# SAMD21_Xplained_Pro_triple_input_power_s.net
KiCad netlist of a schematic drawn in Altium Designer
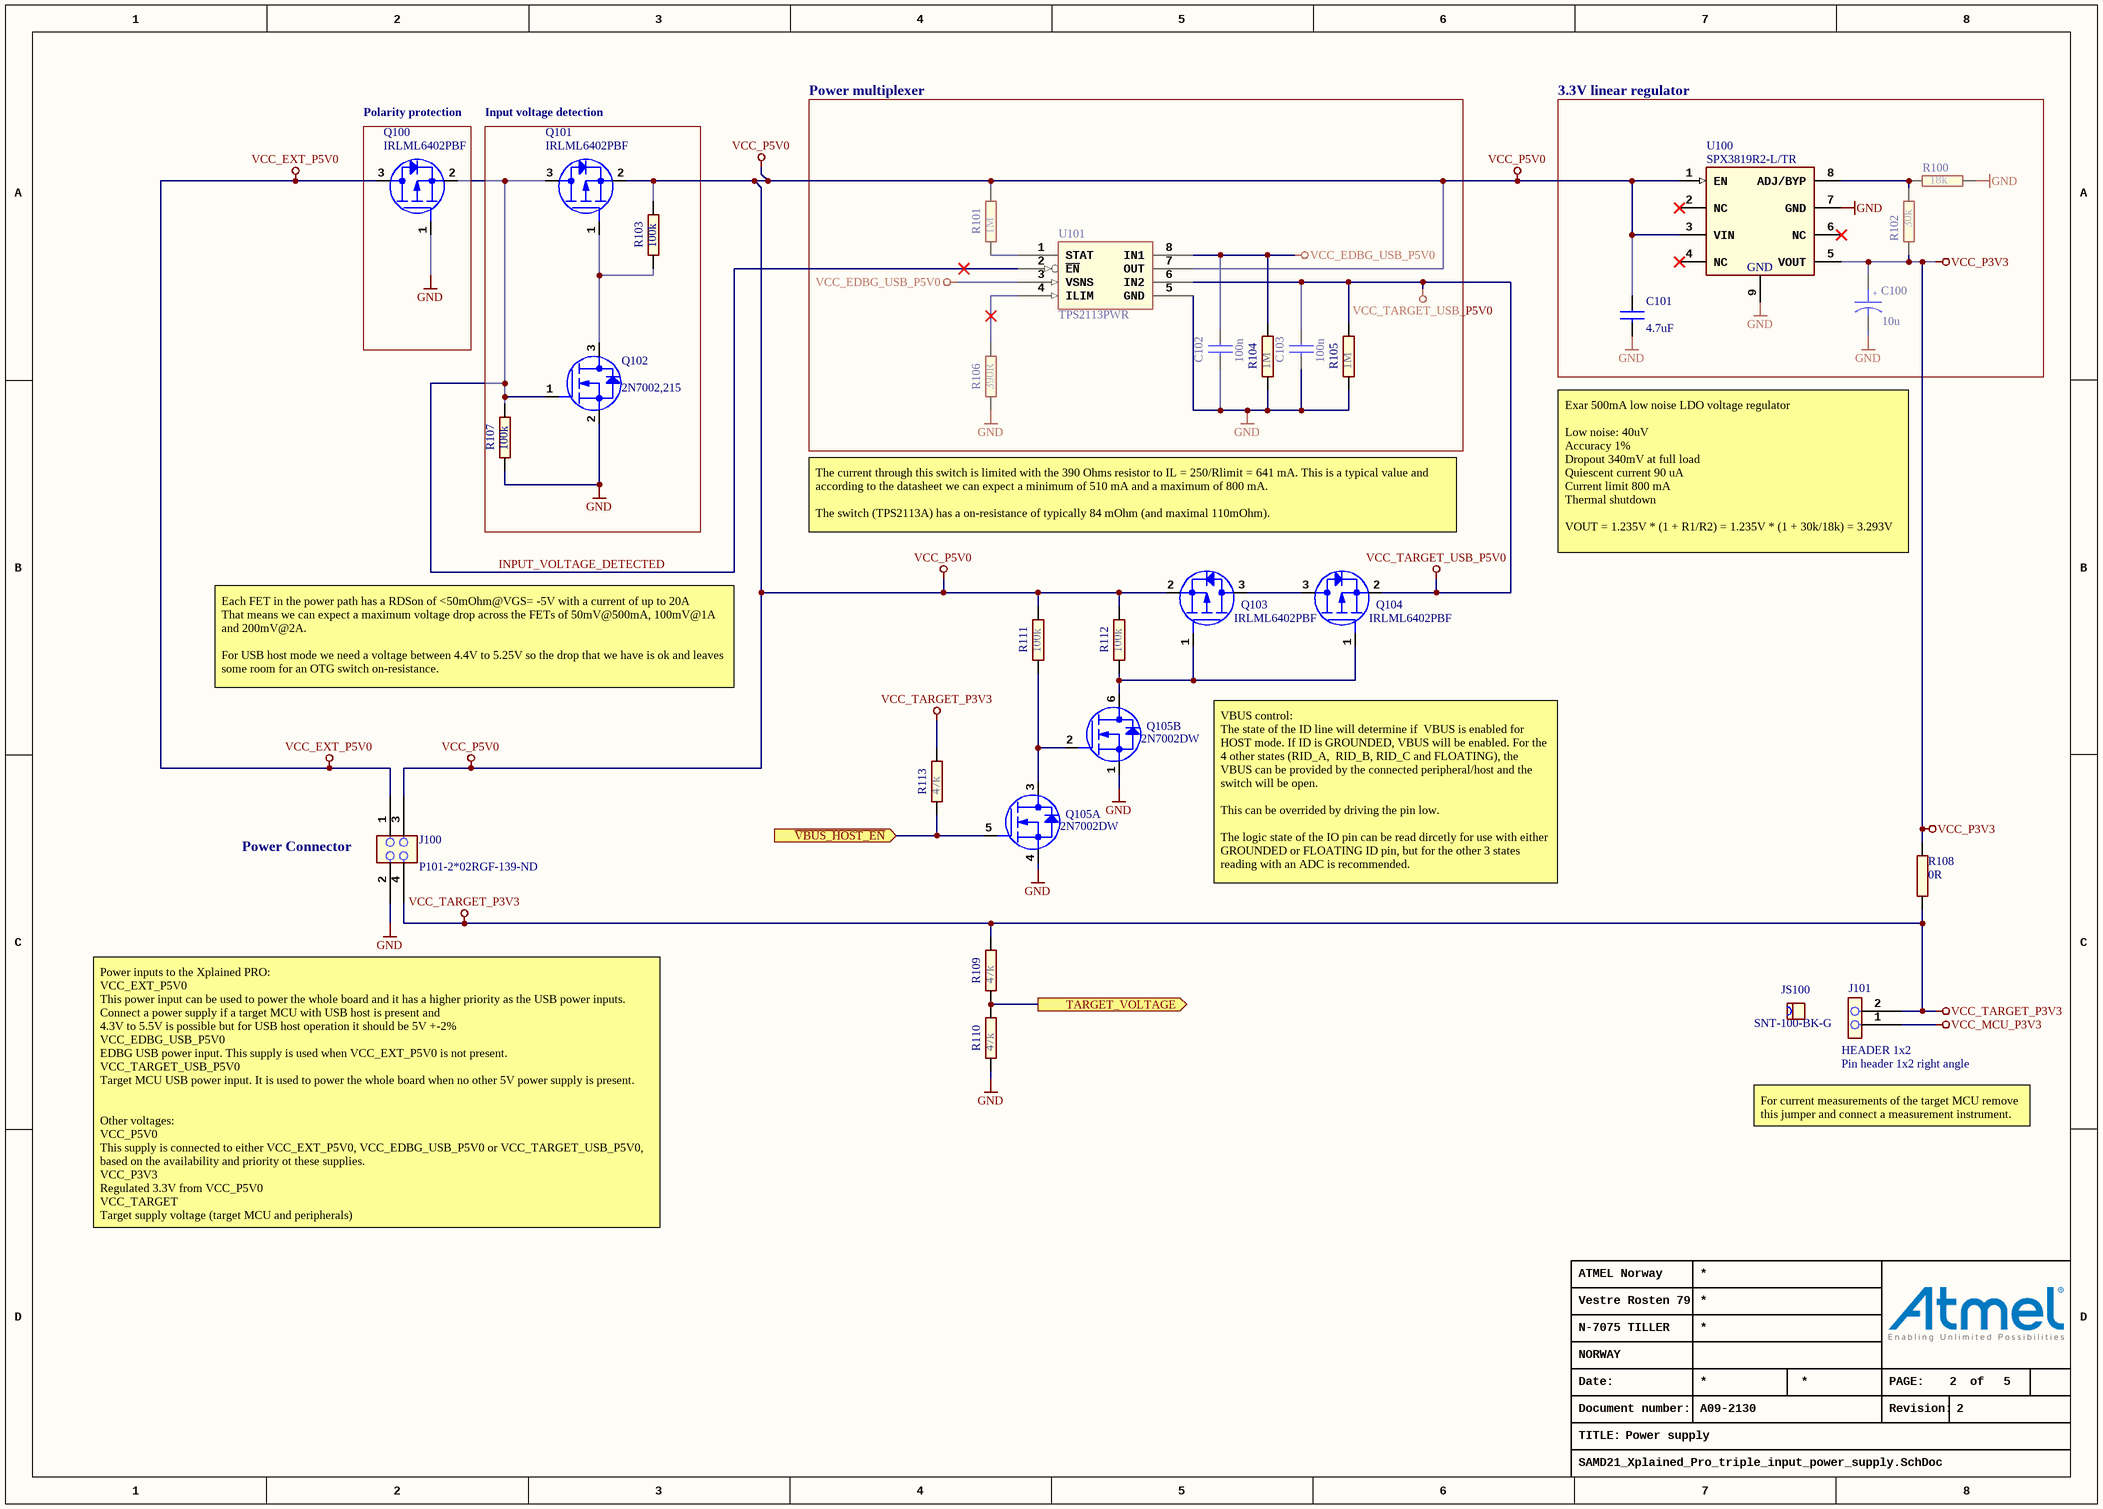
[diagram p0: SAMD21_Xplained_Pro_triple_input_power_supply.SchDoc]

(export (version "E")
  (design (tool "Eeschema 10.0.6"))
  (components
    (comp (ref "C100")
      (value "10u")
      (footprint "AP1-00036")
      (description "SMD tantalum capacitor, ESR = 1.7, 3216-18 (EIA) 1206,")
      (fields (field (name "TOLERANCE") "+-10%") (field (name "MANUFACTURER") "vishay"))
      (libsource (lib "AltiumDbLib") (part "CAP-POL"))
    )
    (comp (ref "C101")
      (value "4.7uF")
      (footprint "AP1-00039")
      (description "Ceramic capacitor, SMD 0603, X5R, 10V, 10% (de31036)")
      (fields (field (name "TOLERANCE") "10%") (field (name "MANUFACTURER") "tdk"))
      (libsource (lib "AltiumDbLib") (part "CAP-NONPOL"))
    )
    (comp (ref "C102")
      (value "100n")
      (footprint "AP1-00001")
      (description "Ceramic capacitor, SMD 0402, X7R, 16V, +/-10%")
      (fields (field (name "TOLERANCE") "16V, +/-10%") (field (name "MANUFACTURER") "Kemet"))
      (libsource (lib "AltiumDbLib") (part "CAP-NONPOL"))
    )
    (comp (ref "C103")
      (value "100n")
      (footprint "AP1-00001")
      (description "Ceramic capacitor, SMD 0402, X7R, 16V, +/-10%")
      (fields (field (name "TOLERANCE") "16V, +/-10%") (field (name "MANUFACTURER") "Kemet"))
      (libsource (lib "AltiumDbLib") (part "CAP-NONPOL"))
    )
    (comp (ref "J100")
      (value "P101-2*02RGF-139-ND")
      (footprint "AP8-00628")
      (description "Pin header, 2x2, Right Angle, 2.54mm, THT, Pin In Paste")
      (fields (field (name "Comment") "HEADER 2x2"))
      (libsource (lib "AltiumDbLib") (part "HEADER 2x2"))
    )
    (comp (ref "J101")
      (value "HEADER 1x2")
      (footprint "AP8-00367")
      (description "1x2 pin header, right angle, 2.54 mm pitch, through-hole")
      (fields
        (field (name "ALTIUM_VALUE") "Pin header 1x2 right angle")
        (field (name "MANUFACTURER") "Pro-data International Corp")
        (field (name "MPN") "2213R-2G")
      )
      (libsource (lib "AltiumDbLib") (part "HEADER 1x2"))
    )
    (comp (ref "JS100")
      (value "SNT-100-BK-G")
      (footprint "AP8-00525")
      (description "Jumper cap for 2.54mm pinheader")
      (fields (field (name "MANUFACTURER") "SAMTEC"))
      (libsource (lib "AltiumDbLib") (part "JUMPER_CAP"))
    )
    (comp (ref "Q100")
      (value "IRLML6402PBF")
      (footprint "AP5-00002")
      (description "P-ch. MOSFET. -30V, -3.7A continuous,RDS(ON)=0.05Ohm@VGS=-4,5V, RDS(ON)=0.08Ohm@VGS=-2.5V")
      (fields (field (name "MANUFACTURER") "International Rectifier") (field (name "Comment") "MOSFET_P_GSD"))
      (libsource (lib "AltiumDbLib") (part "MOSFET_P_GSD"))
    )
    (comp (ref "Q101")
      (value "IRLML6402PBF")
      (footprint "AP5-00002")
      (description "P-ch. MOSFET. -30V, -3.7A continuous,RDS(ON)=0.05Ohm@VGS=-4,5V, RDS(ON)=0.08Ohm@VGS=-2.5V")
      (fields (field (name "MANUFACTURER") "International Rectifier") (field (name "Comment") "MOSFET_P_GSD"))
      (libsource (lib "AltiumDbLib") (part "MOSFET_P_GSD"))
    )
    (comp (ref "Q102")
      (value "2N7002,215")
      (footprint "AP5-00002")
      (description "N-Channel MOSFET. 60V, 0.300A continuous, 1.2A Peak. RDS(ON) = 3.8Ohm@VGS=4.5V, VGS(th)<2.5V")
      (fields (field (name "MANUFACTURER") "NXP") (field (name "Comment") "MOSFET_N_GSD"))
      (libsource (lib "AltiumDbLib") (part "MOSFET_N_GSD"))
    )
    (comp (ref "Q103")
      (value "IRLML6402PBF")
      (footprint "AP5-00002")
      (description "P-ch. MOSFET. -30V, -3.7A continuous,RDS(ON)=0.05Ohm@VGS=-4,5V, RDS(ON)=0.08Ohm@VGS=-2.5V")
      (fields (field (name "MANUFACTURER") "International Rectifier") (field (name "Comment") "MOSFET_P_GSD"))
      (libsource (lib "AltiumDbLib") (part "MOSFET_P_GSD"))
    )
    (comp (ref "Q104")
      (value "IRLML6402PBF")
      (footprint "AP5-00002")
      (description "P-ch. MOSFET. -30V, -3.7A continuous,RDS(ON)=0.05Ohm@VGS=-4,5V, RDS(ON)=0.08Ohm@VGS=-2.5V")
      (fields (field (name "MANUFACTURER") "International Rectifier") (field (name "Comment") "MOSFET_P_GSD"))
      (libsource (lib "AltiumDbLib") (part "MOSFET_P_GSD"))
    )
    (comp (ref "Q105")
      (value "2N7002DW")
      (footprint "AP5-00001")
      (description "Dual N-Channel MOSFET, 60V, 115mA cont,RDS(ON) < 7.5 Ohm @50mA@5V, SOT-363")
      (fields
        (field (name "MANUFACTURER") "Fairchild")
        (field (name "Comment") "Same as 2N7002 but with two MOSFETs in one package")
      )
      (libsource (lib "AltiumDbLib") (part "MOSFET_DUAL_N_S2G2D1S1G1D2"))
    )
    (comp (ref "R100")
      (value "18k")
      (footprint "AP2-00000")
      (description "Thick film resistor, SMD 0402, 1/16W, 1%")
      (fields (field (name "TOLERANCE") "1 %") (field (name "Comment") "R2"))
      (libsource (lib "") (part "R2_3"))
    )
    (comp (ref "R101")
      (value "1M")
      (footprint "AP2-00000")
      (description "Thick film resistor, SMD 0402, 1/16W, 1%")
      (fields (field (name "TOLERANCE") "1 %") (field (name "Comment") "R2"))
      (libsource (lib "") (part "R2_1"))
    )
    (comp (ref "R102")
      (value "30k")
      (footprint "AP2-00000")
      (description "Thick film resistor, SMD 0402, 1/16W, 1%")
      (fields (field (name "TOLERANCE") "1 %") (field (name "Comment") "R2"))
      (libsource (lib "") (part "R2_1"))
    )
    (comp (ref "R103")
      (value "100k")
      (footprint "AP2-00000")
      (description "Thick film resistor, SMD 0402, 1/16W, 1%")
      (fields (field (name "TOLERANCE") "1 %") (field (name "Comment") "R2"))
      (libsource (lib "") (part "R2_1"))
    )
    (comp (ref "R104")
      (value "1M")
      (footprint "AP2-00000")
      (description "Thick film resistor, SMD 0402, 1/16W, 1%")
      (fields (field (name "TOLERANCE") "1 %") (field (name "Comment") "R2"))
      (libsource (lib "") (part "R2_1"))
    )
    (comp (ref "R105")
      (value "1M")
      (footprint "AP2-00000")
      (description "Thick film resistor, SMD 0402, 1/16W, 1%")
      (fields (field (name "TOLERANCE") "1 %") (field (name "Comment") "R2"))
      (libsource (lib "") (part "R2_1"))
    )
    (comp (ref "R106")
      (value "390R")
      (footprint "AP2-00000")
      (description "Thick film resistor, SMD 0402, 1/16W, 1%")
      (fields (field (name "TOLERANCE") "1 %") (field (name "Comment") "R2"))
      (libsource (lib "") (part "R2_1"))
    )
    (comp (ref "R107")
      (value "100k")
      (footprint "AP2-00000")
      (description "Thick film resistor, SMD 0402, 1/16W, 1%")
      (fields (field (name "TOLERANCE") "1 %") (field (name "Comment") "R2"))
      (libsource (lib "") (part "R2_1"))
    )
    (comp (ref "R108")
      (value "0R")
      (footprint "AP2-00000")
      (description "Thick film resistor, SMD 0402, 1/16W, 1%")
      (fields (field (name "TOLERANCE") "1 %") (field (name "Comment") "R2"))
      (libsource (lib "AltiumDbLib") (part "R2"))
    )
    (comp (ref "R109")
      (value "47k")
      (footprint "AP2-00000")
      (description "Thick film resistor, SMD 0402, 1/16W, 1%")
      (fields (field (name "TOLERANCE") "1 %") (field (name "Comment") "R2"))
      (libsource (lib "") (part "R2_2"))
    )
    (comp (ref "R110")
      (value "47k")
      (footprint "AP2-00000")
      (description "Thick film resistor, SMD 0402, 1/16W, 1%")
      (fields (field (name "TOLERANCE") "1 %") (field (name "Comment") "R2"))
      (libsource (lib "") (part "R2_2"))
    )
    (comp (ref "R111")
      (value "100k")
      (footprint "AP2-00000")
      (description "Thick film resistor, SMD 0402, 1/16W, 1%")
      (fields (field (name "TOLERANCE") "1 %") (field (name "Comment") "R2"))
      (libsource (lib "") (part "R2_1"))
    )
    (comp (ref "R112")
      (value "100k")
      (footprint "AP2-00000")
      (description "Thick film resistor, SMD 0402, 1/16W, 1%")
      (fields (field (name "TOLERANCE") "1 %") (field (name "Comment") "R2"))
      (libsource (lib "AltiumDbLib") (part "R2"))
    )
    (comp (ref "R113")
      (value "47k")
      (footprint "AP2-00000")
      (description "Thick film resistor, SMD 0402, 1/16W, 1%")
      (fields (field (name "TOLERANCE") "1 %") (field (name "Comment") "R2"))
      (libsource (lib "") (part "R2_2"))
    )
    (comp (ref "U100")
      (value "SPX3819R2-L/TR")
      (footprint "AP6-00338")
      (description "500mA LDO, ADJ, low noise, 8-DFN package")
      (fields (field (name "TOLERANCE") "±1%") (field (name "MANUFACTURER") "Exar"))
      (libsource (lib "AltiumDbLib") (part "SPX3819R2-L"))
    )
    (comp (ref "U101")
      (value "TPS2113PWR")
      (footprint "AP6-00054")
      (description "Autoswitching 2:1 Power Mux")
      (fields (field (name "MANUFACTURER") "Texas Instruments") (field (name "Comment") "TPS2112"))
      (libsource (lib "AltiumDbLib") (part "TPS2112"))
    )
  )
  (nets
    (net (code "1") (name "/INPUT_VOLTAGE_DETECTED") (class "Default")
      (node (ref "Q100") (pin "2") (pinfunction "S_2") (pintype "passive"))
      (node (ref "Q101") (pin "3") (pinfunction "D_3") (pintype "passive"))
      (node (ref "Q102") (pin "1") (pinfunction "G_1") (pintype "passive"))
      (node (ref "R107") (pin "2") (pinfunction "2_2") (pintype "passive"))
      (node (ref "U101") (pin "2") (pinfunction "~{EN}_2") (pintype "input"))
    )
    (net (code "2") (name "/TARGET_VOLTAGE") (class "Default")
      (node (ref "R109") (pin "1") (pinfunction "1_1") (pintype "passive"))
      (node (ref "R110") (pin "2") (pinfunction "2_2") (pintype "passive"))
    )
    (net (code "3") (name "/~{VBUS_HOST_EN}") (class "Default")
      (node (ref "Q105") (pin "5") (pinfunction "G1_5") (pintype "passive"))
      (node (ref "R113") (pin "1") (pinfunction "1_1") (pintype "passive"))
    )
    (net (code "4") (name "GND") (class "Default")
      (node (ref "C100") (pin "2") (pinfunction "2_2") (pintype "passive"))
      (node (ref "C101") (pin "2") (pinfunction "2_2") (pintype "passive"))
      (node (ref "C102") (pin "2") (pinfunction "2_2") (pintype "passive"))
      (node (ref "C103") (pin "2") (pinfunction "2_2") (pintype "passive"))
      (node (ref "J100") (pin "2") (pinfunction "2_2") (pintype "passive"))
      (node (ref "Q100") (pin "1") (pinfunction "G_1") (pintype "passive"))
      (node (ref "Q102") (pin "2") (pinfunction "S_2") (pintype "passive"))
      (node (ref "Q105") (pin "1") (pinfunction "S2_1") (pintype "passive"))
      (node (ref "Q105") (pin "4") (pinfunction "S1_4") (pintype "passive"))
      (node (ref "R100") (pin "2") (pinfunction "2_2") (pintype "passive"))
      (node (ref "R104") (pin "1") (pinfunction "1_1") (pintype "passive"))
      (node (ref "R105") (pin "1") (pinfunction "1_1") (pintype "passive"))
      (node (ref "R106") (pin "1") (pinfunction "1_1") (pintype "passive"))
      (node (ref "R107") (pin "1") (pinfunction "1_1") (pintype "passive"))
      (node (ref "R110") (pin "1") (pinfunction "1_1") (pintype "passive"))
      (node (ref "U100") (pin "7") (pinfunction "GND_7") (pintype "power_in"))
      (node (ref "U100") (pin "9") (pinfunction "GND_9") (pintype "power_in"))
      (node (ref "U101") (pin "5") (pinfunction "GND_5") (pintype "power_in"))
    )
    (net (code "5") (name "Net-(Q101-G)") (class "Default")
      (node (ref "Q101") (pin "1") (pinfunction "G_1") (pintype "passive"))
      (node (ref "Q102") (pin "3") (pinfunction "D_3") (pintype "passive"))
      (node (ref "R103") (pin "1") (pinfunction "1_1") (pintype "passive"))
    )
    (net (code "6") (name "Net-(Q103-D)") (class "Default")
      (node (ref "Q103") (pin "3") (pinfunction "D_3") (pintype "passive"))
      (node (ref "Q104") (pin "3") (pinfunction "D_3") (pintype "passive"))
    )
    (net (code "7") (name "Net-(Q103-G)") (class "Default")
      (node (ref "Q103") (pin "1") (pinfunction "G_1") (pintype "passive"))
      (node (ref "Q104") (pin "1") (pinfunction "G_1") (pintype "passive"))
      (node (ref "Q105") (pin "6") (pinfunction "D2_6") (pintype "passive"))
      (node (ref "R112") (pin "2") (pinfunction "2_2") (pintype "passive"))
    )
    (net (code "8") (name "Net-(Q105A-D1)") (class "Default")
      (node (ref "Q105") (pin "2") (pinfunction "G2_2") (pintype "passive"))
      (node (ref "Q105") (pin "3") (pinfunction "D1_3") (pintype "passive"))
      (node (ref "R111") (pin "1") (pinfunction "1_1") (pintype "passive"))
    )
    (net (code "9") (name "Net-(U100-ADJ{slash}BYP)") (class "Default")
      (node (ref "R100") (pin "1") (pinfunction "1_1") (pintype "passive"))
      (node (ref "R102") (pin "2") (pinfunction "2_2") (pintype "passive"))
      (node (ref "U100") (pin "8") (pinfunction "ADJ/BYP_8") (pintype "passive"))
    )
    (net (code "10") (name "Net-(U101-ILIM)") (class "Default")
      (node (ref "R106") (pin "2") (pinfunction "2_2") (pintype "passive"))
      (node (ref "U101") (pin "4") (pinfunction "ILIM_4") (pintype "input"))
    )
    (net (code "11") (name "Net-(U101-STAT)") (class "Default")
      (node (ref "R101") (pin "1") (pinfunction "1_1") (pintype "passive"))
      (node (ref "U101") (pin "1") (pinfunction "STAT_1") (pintype "open_collector"))
    )
    (net (code "12") (name "VCC_EDBG_USB_P5V0") (class "Default")
      (node (ref "C102") (pin "1") (pinfunction "1_1") (pintype "passive"))
      (node (ref "R104") (pin "2") (pinfunction "2_2") (pintype "passive"))
      (node (ref "U101") (pin "3") (pinfunction "VSNS_3") (pintype "input"))
      (node (ref "U101") (pin "8") (pinfunction "IN1_8") (pintype "power_in"))
    )
    (net (code "13") (name "VCC_EXT_P5V0") (class "Default")
      (node (ref "J100") (pin "1") (pinfunction "1_1") (pintype "passive"))
      (node (ref "Q100") (pin "3") (pinfunction "D_3") (pintype "passive"))
    )
    (net (code "14") (name "VCC_MCU_P3V3") (class "Default")
      (node (ref "J101") (pin "1") (pinfunction "1_1") (pintype "passive"))
    )
    (net (code "15") (name "VCC_P3V3") (class "Default")
      (node (ref "C100") (pin "1") (pinfunction "1_1") (pintype "passive"))
      (node (ref "R102") (pin "1") (pinfunction "1_1") (pintype "passive"))
      (node (ref "R108") (pin "1") (pinfunction "1_1") (pintype "passive"))
      (node (ref "U100") (pin "5") (pinfunction "VOUT_5") (pintype "power_in"))
    )
    (net (code "16") (name "VCC_P5V0") (class "Default")
      (node (ref "C101") (pin "1") (pinfunction "1_1") (pintype "passive"))
      (node (ref "J100") (pin "3") (pinfunction "3_3") (pintype "passive"))
      (node (ref "Q101") (pin "2") (pinfunction "S_2") (pintype "passive"))
      (node (ref "Q103") (pin "2") (pinfunction "S_2") (pintype "passive"))
      (node (ref "R101") (pin "2") (pinfunction "2_2") (pintype "passive"))
      (node (ref "R103") (pin "2") (pinfunction "2_2") (pintype "passive"))
      (node (ref "R111") (pin "2") (pinfunction "2_2") (pintype "passive"))
      (node (ref "R112") (pin "1") (pinfunction "1_1") (pintype "passive"))
      (node (ref "U100") (pin "1") (pinfunction "EN_1") (pintype "input"))
      (node (ref "U100") (pin "3") (pinfunction "VIN_3") (pintype "power_in"))
      (node (ref "U101") (pin "7") (pinfunction "OUT_7") (pintype "power_in"))
    )
    (net (code "17") (name "VCC_TARGET_P3V3") (class "Default")
      (node (ref "J100") (pin "4") (pinfunction "4_4") (pintype "passive"))
      (node (ref "J101") (pin "2") (pinfunction "2_2") (pintype "passive"))
      (node (ref "R108") (pin "2") (pinfunction "2_2") (pintype "passive"))
      (node (ref "R109") (pin "2") (pinfunction "2_2") (pintype "passive"))
      (node (ref "R113") (pin "2") (pinfunction "2_2") (pintype "passive"))
    )
    (net (code "18") (name "VCC_TARGET_USB_P5V0") (class "Default")
      (node (ref "C103") (pin "1") (pinfunction "1_1") (pintype "passive"))
      (node (ref "Q104") (pin "2") (pinfunction "S_2") (pintype "passive"))
      (node (ref "R105") (pin "2") (pinfunction "2_2") (pintype "passive"))
      (node (ref "U101") (pin "6") (pinfunction "IN2_6") (pintype "power_in"))
    )
    (net (code "19") (name "unconnected-(U100-NC-Pad2)") (class "Default")
      (node (ref "U100") (pin "2") (pinfunction "NC_2") (pintype "passive+no_connect"))
    )
    (net (code "20") (name "unconnected-(U100-NC-Pad4)") (class "Default")
      (node (ref "U100") (pin "4") (pinfunction "NC_4") (pintype "passive+no_connect"))
    )
    (net (code "21") (name "unconnected-(U100-NC-Pad6)") (class "Default")
      (node (ref "U100") (pin "6") (pinfunction "NC_6") (pintype "passive+no_connect"))
    )
  )
)
